# SparkFun_USDA_Watershed_Monitor.net
KiCad netlist of a schematic drawn in EAGLE
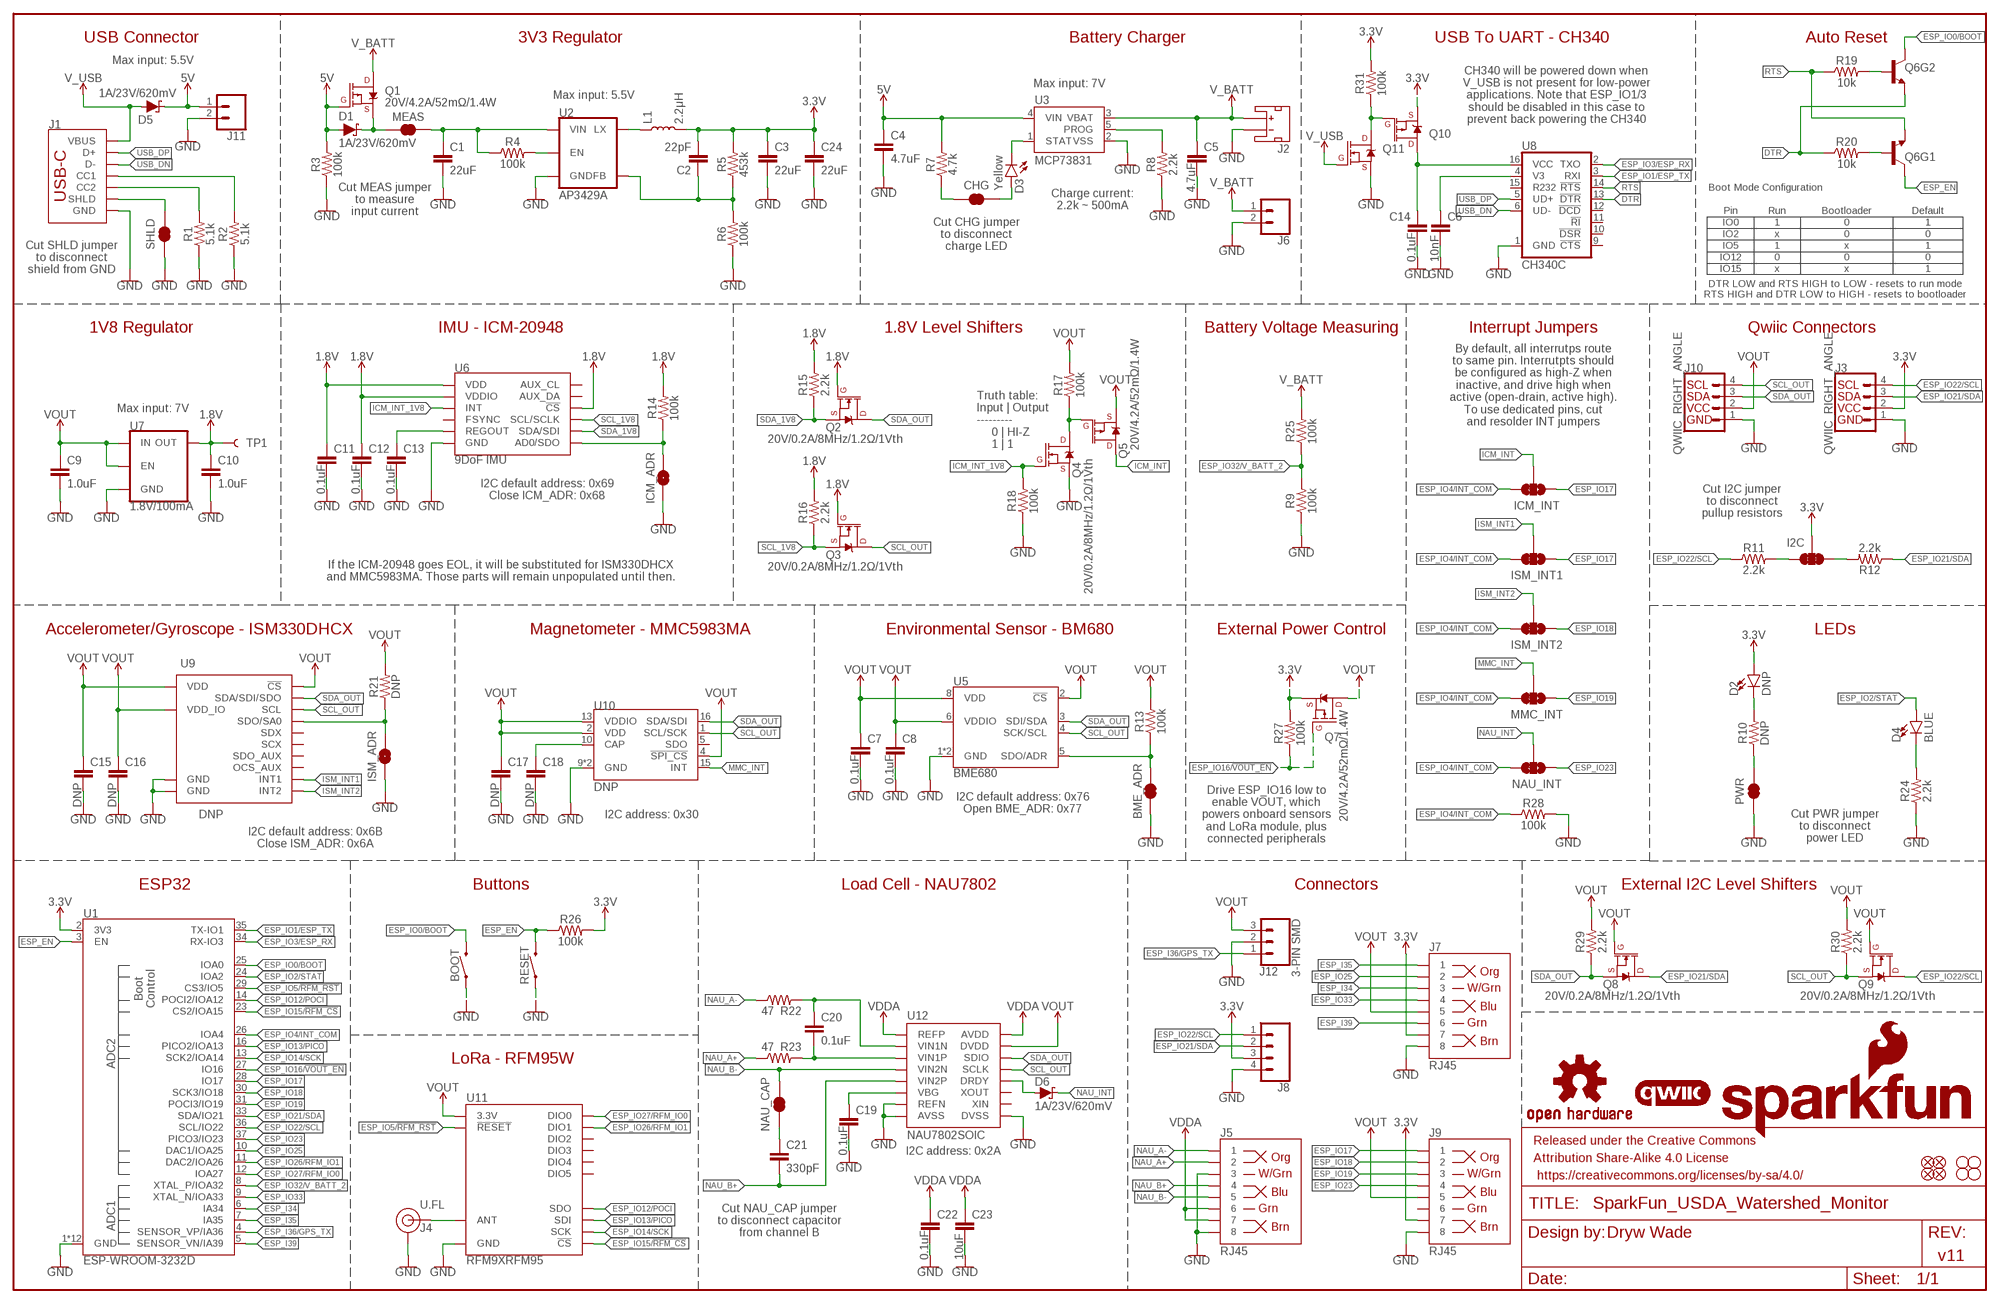
[diagram p0: schematic, sheet 1]

(export (version "E")
  (design (tool "Eeschema 10.0.6"))
  (components
    (comp (ref "BME_ADR")
      (value "JUMPER-SMT_2_NC_TRACE_SILK")
      (footprint "eagle-import:SMT-JUMPER_2_NC_TRACE_SILK")
      (libsource (lib "eagle-import") (part "JUMPER-SMT_2_NC_TRACE_SILK"))
    )
    (comp (ref "BOOT")
      (value "MOMENTARY-SWITCH-SPST-SMD-4.6X2.8MM")
      (footprint "eagle-import:TACTILE_SWITCH_SMD_4.6X2.8MM")
      (libsource (lib "eagle-import") (part "MOMENTARY-SWITCH-SPST-SMD-4.6X2.8MM"))
    )
    (comp (ref "C1")
      (value "22uF")
      (footprint "eagle-import:0805")
      (libsource (lib "eagle-import") (part "22UF-0805-16V-20%"))
    )
    (comp (ref "C2")
      (value "22pF")
      (footprint "eagle-import:0603")
      (libsource (lib "eagle-import") (part "22PF-0603-50V-5%"))
    )
    (comp (ref "C3")
      (value "22uF")
      (footprint "eagle-import:0805")
      (libsource (lib "eagle-import") (part "22UF-0805-16V-20%"))
    )
    (comp (ref "C4")
      (value "4.7uF")
      (footprint "eagle-import:0603")
      (libsource (lib "eagle-import") (part "4.7UF-0603-6.3V-(10%)"))
    )
    (comp (ref "C5")
      (value "4.7uF")
      (footprint "eagle-import:0603")
      (libsource (lib "eagle-import") (part "4.7UF-0603-6.3V-(10%)"))
    )
    (comp (ref "C6")
      (value "10nF")
      (footprint "eagle-import:0603")
      (libsource (lib "eagle-import") (part "10NF-0603-50V-10%"))
    )
    (comp (ref "C7")
      (value "0.1uF")
      (footprint "eagle-import:0603")
      (libsource (lib "eagle-import") (part "0.1UF-0603-25V-(+80/-20%)"))
    )
    (comp (ref "C8")
      (value "0.1uF")
      (footprint "eagle-import:0603")
      (libsource (lib "eagle-import") (part "0.1UF-0603-25V-(+80/-20%)"))
    )
    (comp (ref "C9")
      (value "1.0uF")
      (footprint "eagle-import:0603")
      (libsource (lib "eagle-import") (part "1.0UF-0603-16V-10%"))
    )
    (comp (ref "C10")
      (value "1.0uF")
      (footprint "eagle-import:0603")
      (libsource (lib "eagle-import") (part "1.0UF-0603-16V-10%"))
    )
    (comp (ref "C11")
      (value "0.1uF")
      (footprint "eagle-import:0603")
      (libsource (lib "eagle-import") (part "0.1UF-0603-25V-(+80/-20%)"))
    )
    (comp (ref "C12")
      (value "0.1uF")
      (footprint "eagle-import:0603")
      (libsource (lib "eagle-import") (part "0.1UF-0603-25V-(+80/-20%)"))
    )
    (comp (ref "C13")
      (value "0.1uF")
      (footprint "eagle-import:0603")
      (libsource (lib "eagle-import") (part "0.1UF-0603-25V-(+80/-20%)"))
    )
    (comp (ref "C14")
      (value "0.1uF")
      (footprint "eagle-import:0603")
      (libsource (lib "eagle-import") (part "0.1UF-0603-25V-(+80/-20%)"))
    )
    (comp (ref "C15")
      (value "DNP")
      (footprint "eagle-import:0603")
      (libsource (lib "eagle-import") (part "0.1UF-0603-25V-(+80/-20%)"))
    )
    (comp (ref "C16")
      (value "DNP")
      (footprint "eagle-import:0603")
      (libsource (lib "eagle-import") (part "0.1UF-0603-25V-(+80/-20%)"))
    )
    (comp (ref "C17")
      (value "DNP")
      (footprint "eagle-import:0603")
      (libsource (lib "eagle-import") (part "1.0UF-0603-16V-10%"))
    )
    (comp (ref "C18")
      (value "DNP")
      (footprint "eagle-import:0603")
      (libsource (lib "eagle-import") (part "10UF-0603-6.3V-20%"))
    )
    (comp (ref "C19")
      (value "0.1uF")
      (footprint "eagle-import:0603")
      (libsource (lib "eagle-import") (part "0.1UF-0603-25V-(+80/-20%)"))
    )
    (comp (ref "C20")
      (value "0.1uF")
      (footprint "eagle-import:0603")
      (libsource (lib "eagle-import") (part "0.1UF-0603-25V-(+80/-20%)"))
    )
    (comp (ref "C21")
      (value "330pF")
      (footprint "eagle-import:0603")
      (libsource (lib "eagle-import") (part "330PF-0603-50V-5%"))
    )
    (comp (ref "C22")
      (value "0.1uF")
      (footprint "eagle-import:0603")
      (libsource (lib "eagle-import") (part "0.1UF-0603-25V-(+80/-20%)"))
    )
    (comp (ref "C23")
      (value "10uF")
      (footprint "eagle-import:0603")
      (libsource (lib "eagle-import") (part "10UF-0603-6.3V-20%"))
    )
    (comp (ref "C24")
      (value "22uF")
      (footprint "eagle-import:0805")
      (libsource (lib "eagle-import") (part "22UF-0805-16V-20%"))
    )
    (comp (ref "CHG")
      (value "JUMPER-SMT_2_NC_TRACE_SILK")
      (footprint "eagle-import:SMT-JUMPER_2_NC_TRACE_SILK")
      (libsource (lib "eagle-import") (part "JUMPER-SMT_2_NC_TRACE_SILK"))
    )
    (comp (ref "D1")
      (value "1A/23V/620mV")
      (footprint "eagle-import:SOD-323")
      (libsource (lib "eagle-import") (part "DIODE-SCHOTTKY-BAT20J"))
    )
    (comp (ref "D2")
      (value "DNP")
      (footprint "eagle-import:LED-0603")
      (libsource (lib "eagle-import") (part "LED-RED_0603-KB"))
    )
    (comp (ref "D3")
      (value "Yellow")
      (footprint "eagle-import:LED-0603")
      (libsource (lib "eagle-import") (part "LED-YELLOW0603"))
    )
    (comp (ref "D4")
      (value "BLUE")
      (footprint "eagle-import:LED-0603")
      (libsource (lib "eagle-import") (part "LED-BLUE0603"))
    )
    (comp (ref "D5")
      (value "1A/23V/620mV")
      (footprint "eagle-import:SOD-323")
      (libsource (lib "eagle-import") (part "DIODE-SCHOTTKY-BAT20J"))
    )
    (comp (ref "D6")
      (value "1A/23V/620mV")
      (footprint "eagle-import:SOD-323")
      (libsource (lib "eagle-import") (part "DIODE-SCHOTTKY-BAT20J"))
    )
    (comp (ref "FD1")
      (value "FIDUCIAL1X2")
      (footprint "eagle-import:FIDUCIAL-1X2")
      (libsource (lib "eagle-import") (part "FIDUCIAL1X2"))
    )
    (comp (ref "FD2")
      (value "FIDUCIAL1X2")
      (footprint "eagle-import:FIDUCIAL-1X2")
      (libsource (lib "eagle-import") (part "FIDUCIAL1X2"))
    )
    (comp (ref "FD3")
      (value "FIDUCIAL1X2")
      (footprint "eagle-import:FIDUCIAL-1X2")
      (libsource (lib "eagle-import") (part "FIDUCIAL1X2"))
    )
    (comp (ref "FD4")
      (value "FIDUCIAL1X2")
      (footprint "eagle-import:FIDUCIAL-1X2")
      (libsource (lib "eagle-import") (part "FIDUCIAL1X2"))
    )
    (comp (ref "FRAME1")
      (value "FRAME-LEDGER")
      (footprint "eagle-import:CREATIVE_COMMONS")
      (libsource (lib "eagle-import") (part "FRAME-LEDGER"))
    )
    (comp (ref "H1")
      (value "STAND-OFF")
      (footprint "eagle-import:STAND-OFF")
      (libsource (lib "eagle-import") (part "STAND-OFF"))
    )
    (comp (ref "H2")
      (value "STAND-OFF")
      (footprint "eagle-import:STAND-OFF")
      (libsource (lib "eagle-import") (part "STAND-OFF"))
    )
    (comp (ref "H3")
      (value "STAND-OFF")
      (footprint "eagle-import:STAND-OFF")
      (libsource (lib "eagle-import") (part "STAND-OFF"))
    )
    (comp (ref "H4")
      (value "STAND-OFF")
      (footprint "eagle-import:STAND-OFF")
      (libsource (lib "eagle-import") (part "STAND-OFF"))
    )
    (comp (ref "I2C")
      (value "JUMPER-SMT_3_2-NC_TRACE_SILK")
      (footprint "eagle-import:SMT-JUMPER_3_2-NC_TRACE_SILK")
      (libsource (lib "eagle-import") (part "JUMPER-SMT_3_2-NC_TRACE_SILK"))
    )
    (comp (ref "ICM_ADR")
      (value "JUMPER-SMT_2_NO_SILK")
      (footprint "eagle-import:SMT-JUMPER_2_NO_SILK")
      (libsource (lib "eagle-import") (part "JUMPER-SMT_2_NO_SILK"))
    )
    (comp (ref "ICM_INT")
      (value "JUMPER-SMT_3_1-NC_TRACE_SILK")
      (footprint "eagle-import:SMT-JUMPER_3_1-NC_TRACE_SILK")
      (libsource (lib "eagle-import") (part "JUMPER-SMT_3_1-NC_TRACE_SILK"))
    )
    (comp (ref "ISM_ADR")
      (value "JUMPER-SMT_2_NO_SILK")
      (footprint "eagle-import:SMT-JUMPER_2_NO_SILK")
      (libsource (lib "eagle-import") (part "JUMPER-SMT_2_NO_SILK"))
    )
    (comp (ref "ISM_INT1")
      (value "JUMPER-SMT_3_1-NC_TRACE_SILK")
      (footprint "eagle-import:SMT-JUMPER_3_1-NC_TRACE_SILK")
      (libsource (lib "eagle-import") (part "JUMPER-SMT_3_1-NC_TRACE_SILK"))
    )
    (comp (ref "ISM_INT2")
      (value "JUMPER-SMT_3_1-NC_TRACE_SILK")
      (footprint "eagle-import:SMT-JUMPER_3_1-NC_TRACE_SILK")
      (libsource (lib "eagle-import") (part "JUMPER-SMT_3_1-NC_TRACE_SILK"))
    )
    (comp (ref "J1")
      (value "USB_C_2-LAYER_PADS")
      (footprint "eagle-import:USB-C-16P-2LAYER-PADS")
      (libsource (lib "eagle-import") (part "USB_C_2-LAYER_PADS"))
    )
    (comp (ref "J2")
      (value "JST_2MM_MALE")
      (footprint "eagle-import:JST-2-SMD")
      (libsource (lib "eagle-import") (part "JST_2MM_MALE"))
    )
    (comp (ref "J3")
      (value "QWIIC_RIGHT_ANGLE")
      (footprint "eagle-import:JST04_1MM_RA")
      (libsource (lib "eagle-import") (part "QWIIC_CONNECTORJS-1MM"))
    )
    (comp (ref "J4")
      (value "U.FL")
      (footprint "eagle-import:U.FL")
      (libsource (lib "eagle-import") (part "U.FL2PIN"))
    )
    (comp (ref "J5")
      (value "RJ45")
      (footprint "eagle-import:RJ45-8")
      (libsource (lib "eagle-import") (part "RJ45-8"))
    )
    (comp (ref "J6")
      (value "CONN_021X02_NO_SILK")
      (footprint "eagle-import:1X02_NO_SILK")
      (libsource (lib "eagle-import") (part "CONN_021X02_NO_SILK"))
    )
    (comp (ref "J7")
      (value "RJ45")
      (footprint "eagle-import:RJ45-8")
      (libsource (lib "eagle-import") (part "RJ45-8"))
    )
    (comp (ref "J8")
      (value "CONN_041X04_NO_SILK_NO_POP")
      (footprint "eagle-import:1X04_NO_SILK")
      (libsource (lib "eagle-import") (part "CONN_041X04_NO_SILK_NO_POP"))
    )
    (comp (ref "J9")
      (value "RJ45")
      (footprint "eagle-import:RJ45-8")
      (libsource (lib "eagle-import") (part "RJ45-8"))
    )
    (comp (ref "J10")
      (value "QWIIC_RIGHT_ANGLE")
      (footprint "eagle-import:JST04_1MM_RA")
      (libsource (lib "eagle-import") (part "QWIIC_CONNECTORJS-1MM"))
    )
    (comp (ref "J11")
      (value "CONN_021X02_NO_SILK")
      (footprint "eagle-import:1X02_NO_SILK")
      (libsource (lib "eagle-import") (part "CONN_021X02_NO_SILK"))
    )
    (comp (ref "J12")
      (value "3-PIN SMD")
      (footprint "eagle-import:JST-3-SMD")
      (libsource (lib "eagle-import") (part "CONN_03JST-SMD"))
    )
    (comp (ref "L1")
      (value "2.2μH")
      (footprint "eagle-import:INDUCTOR_4X4MM")
      (libsource (lib "eagle-import") (part "2.2μH-4X4-2.2μH-3A-45MOHM"))
    )
    (comp (ref "LOGO1")
      (value "SFE_LOGO_NAME_FLAME.1_INCH")
      (footprint "eagle-import:SFE_LOGO_NAME_FLAME_.1")
      (libsource (lib "eagle-import") (part "SFE_LOGO_NAME_FLAME.1_INCH"))
    )
    (comp (ref "LOGO2")
      (value "OSHW-LOGOS")
      (footprint "eagle-import:OSHW-LOGO-S")
      (libsource (lib "eagle-import") (part "OSHW-LOGOS"))
    )
    (comp (ref "LOGO3")
      (value "QWIIC_LOGO_4MM")
      (footprint "eagle-import:QWIIC_4MM")
      (libsource (lib "eagle-import") (part "QWIIC_LOGO_4MM"))
    )
    (comp (ref "MEAS")
      (value "JUMPER-COMBO_2_NC_TRACE")
      (footprint "eagle-import:COMBO-JUMPER_2_NC_TRACE")
      (libsource (lib "eagle-import") (part "JUMPER-COMBO_2_NC_TRACE"))
    )
    (comp (ref "MMC_INT")
      (value "JUMPER-SMT_3_1-NC_TRACE_SILK")
      (footprint "eagle-import:SMT-JUMPER_3_1-NC_TRACE_SILK")
      (libsource (lib "eagle-import") (part "JUMPER-SMT_3_1-NC_TRACE_SILK"))
    )
    (comp (ref "NAU_CAP")
      (value "JUMPER-SMT_2_NC_TRACE_SILK")
      (footprint "eagle-import:SMT-JUMPER_2_NC_TRACE_SILK")
      (libsource (lib "eagle-import") (part "JUMPER-SMT_2_NC_TRACE_SILK"))
    )
    (comp (ref "NAU_INT")
      (value "JUMPER-SMT_3_1-NC_TRACE_SILK")
      (footprint "eagle-import:SMT-JUMPER_3_1-NC_TRACE_SILK")
      (libsource (lib "eagle-import") (part "JUMPER-SMT_3_1-NC_TRACE_SILK"))
    )
    (comp (ref "PWR")
      (value "JUMPER-SMT_2_NC_TRACE_SILK")
      (footprint "eagle-import:SMT-JUMPER_2_NC_TRACE_SILK")
      (libsource (lib "eagle-import") (part "JUMPER-SMT_2_NC_TRACE_SILK"))
    )
    (comp (ref "Q1")
      (value "20V/4.2A/52mΩ/1.4W")
      (footprint "eagle-import:SOT23-3")
      (libsource (lib "eagle-import") (part "MOSFET_PCH-DMG2305UX-7"))
    )
    (comp (ref "Q2")
      (value "20V/0.2A/8MHz/1.2Ω/1Vth")
      (footprint "eagle-import:SOT-416FL")
      (libsource (lib "eagle-import") (part "MOSFET-NCH-RE1C002UNTCL"))
    )
    (comp (ref "Q3")
      (value "20V/0.2A/8MHz/1.2Ω/1Vth")
      (footprint "eagle-import:SOT-416FL")
      (libsource (lib "eagle-import") (part "MOSFET-NCH-RE1C002UNTCL"))
    )
    (comp (ref "Q4")
      (value "20V/0.2A/8MHz/1.2Ω/1Vth")
      (footprint "eagle-import:SOT-416FL")
      (libsource (lib "eagle-import") (part "MOSFET-NCH-RE1C002UNTCL"))
    )
    (comp (ref "Q5")
      (value "20V/4.2A/52mΩ/1.4W")
      (footprint "eagle-import:SOT23-3")
      (libsource (lib "eagle-import") (part "MOSFET_PCH-DMG2305UX-7"))
    )
    (comp (ref "Q6")
      (value "TRANS_NPN_DUAL-MBT3904DW1T1")
      (footprint "eagle-import:SC70-6")
      (libsource (lib "eagle-import") (part "TRANS_NPN_DUAL-MBT3904DW1T1"))
    )
    (comp (ref "Q7")
      (value "20V/4.2A/52mΩ/1.4W")
      (footprint "eagle-import:SOT23-3")
      (libsource (lib "eagle-import") (part "MOSFET_PCH-DMG2305UX-7"))
    )
    (comp (ref "Q8")
      (value "20V/0.2A/8MHz/1.2Ω/1Vth")
      (footprint "eagle-import:SOT-416FL")
      (libsource (lib "eagle-import") (part "MOSFET-NCH-RE1C002UNTCL"))
    )
    (comp (ref "Q9")
      (value "20V/0.2A/8MHz/1.2Ω/1Vth")
      (footprint "eagle-import:SOT-416FL")
      (libsource (lib "eagle-import") (part "MOSFET-NCH-RE1C002UNTCL"))
    )
    (comp (ref "Q10")
      (value "20V/4.2A/52mΩ/1.4W")
      (footprint "eagle-import:SOT23-3")
      (libsource (lib "eagle-import") (part "MOSFET_PCH-DMG2305UX-7"))
    )
    (comp (ref "Q11")
      (value "20V/0.2A/8MHz/1.2Ω/1Vth")
      (footprint "eagle-import:SOT-416FL")
      (libsource (lib "eagle-import") (part "MOSFET-NCH-RE1C002UNTCL"))
    )
    (comp (ref "R1")
      (value "5.1k")
      (footprint "eagle-import:0603")
      (libsource (lib "eagle-import") (part "5.1KOHM5.1KOHM-0603-1/10W-1%"))
    )
    (comp (ref "R2")
      (value "5.1k")
      (footprint "eagle-import:0603")
      (libsource (lib "eagle-import") (part "5.1KOHM5.1KOHM-0603-1/10W-1%"))
    )
    (comp (ref "R3")
      (value "100k")
      (footprint "eagle-import:0603")
      (libsource (lib "eagle-import") (part "100KOHM-0603-1/10W-1%"))
    )
    (comp (ref "R4")
      (value "100k")
      (footprint "eagle-import:0603")
      (libsource (lib "eagle-import") (part "100KOHM-0603-1/10W-1%"))
    )
    (comp (ref "R5")
      (value "453k")
      (footprint "eagle-import:0603")
      (libsource (lib "eagle-import") (part "453KOHM-0603-1/10W-1%"))
    )
    (comp (ref "R6")
      (value "100k")
      (footprint "eagle-import:0603")
      (libsource (lib "eagle-import") (part "100KOHM-0603-1/10W-1%"))
    )
    (comp (ref "R7")
      (value "4.7k")
      (footprint "eagle-import:0603")
      (libsource (lib "eagle-import") (part "4.7KOHM-0603-1/10W-1%"))
    )
    (comp (ref "R8")
      (value "2.2k")
      (footprint "eagle-import:0603")
      (libsource (lib "eagle-import") (part "2.2KOHM-0603-1/10W-1%"))
    )
    (comp (ref "R9")
      (value "100k")
      (footprint "eagle-import:0603")
      (libsource (lib "eagle-import") (part "100KOHM-0603-1/10W-1%"))
    )
    (comp (ref "R10")
      (value "DNP")
      (footprint "eagle-import:0603")
      (libsource (lib "eagle-import") (part "4.7KOHM-0603-1/10W-1%"))
    )
    (comp (ref "R11")
      (value "2.2k")
      (footprint "eagle-import:0603")
      (libsource (lib "eagle-import") (part "2.2KOHM-0603-1/10W-1%"))
    )
    (comp (ref "R12")
      (value "2.2k")
      (footprint "eagle-import:0603")
      (libsource (lib "eagle-import") (part "2.2KOHM-0603-1/10W-1%"))
    )
    (comp (ref "R13")
      (value "100k")
      (footprint "eagle-import:0603")
      (libsource (lib "eagle-import") (part "100KOHM-0603-1/10W-1%"))
    )
    (comp (ref "R14")
      (value "100k")
      (footprint "eagle-import:0603")
      (libsource (lib "eagle-import") (part "100KOHM-0603-1/10W-1%"))
    )
    (comp (ref "R15")
      (value "2.2k")
      (footprint "eagle-import:0603")
      (libsource (lib "eagle-import") (part "2.2KOHM-0603-1/10W-1%"))
    )
    (comp (ref "R16")
      (value "2.2k")
      (footprint "eagle-import:0603")
      (libsource (lib "eagle-import") (part "2.2KOHM-0603-1/10W-1%"))
    )
    (comp (ref "R17")
      (value "100k")
      (footprint "eagle-import:0603")
      (libsource (lib "eagle-import") (part "100KOHM-0603-1/10W-1%"))
    )
    (comp (ref "R18")
      (value "100k")
      (footprint "eagle-import:0603")
      (libsource (lib "eagle-import") (part "100KOHM-0603-1/10W-1%"))
    )
    (comp (ref "R19")
      (value "10k")
      (footprint "eagle-import:0603")
      (libsource (lib "eagle-import") (part "10KOHM-0603-1/10W-1%"))
    )
    (comp (ref "R20")
      (value "10k")
      (footprint "eagle-import:0603")
      (libsource (lib "eagle-import") (part "10KOHM-0603-1/10W-1%"))
    )
    (comp (ref "R21")
      (value "DNP")
      (footprint "eagle-import:0603")
      (libsource (lib "eagle-import") (part "100KOHM-0603-1/10W-1%"))
    )
    (comp (ref "R22")
      (value "47")
      (footprint "eagle-import:0603")
      (libsource (lib "eagle-import") (part "47OHM-0603-1/10W-1%"))
    )
    (comp (ref "R23")
      (value "47")
      (footprint "eagle-import:0603")
      (libsource (lib "eagle-import") (part "47OHM-0603-1/10W-1%"))
    )
    (comp (ref "R24")
      (value "2.2k")
      (footprint "eagle-import:0603")
      (libsource (lib "eagle-import") (part "2.2KOHM-0603-1/10W-1%"))
    )
    (comp (ref "R25")
      (value "100k")
      (footprint "eagle-import:0603")
      (libsource (lib "eagle-import") (part "100KOHM-0603-1/10W-1%"))
    )
    (comp (ref "R26")
      (value "100k")
      (footprint "eagle-import:0603")
      (libsource (lib "eagle-import") (part "100KOHM-0603-1/10W-1%"))
    )
    (comp (ref "R27")
      (value "100k")
      (footprint "eagle-import:0603")
      (libsource (lib "eagle-import") (part "100KOHM-0603-1/10W-1%"))
    )
    (comp (ref "R28")
      (value "100k")
      (footprint "eagle-import:0603")
      (libsource (lib "eagle-import") (part "100KOHM-0603-1/10W-1%"))
    )
    (comp (ref "R29")
      (value "2.2k")
      (footprint "eagle-import:0603")
      (libsource (lib "eagle-import") (part "2.2KOHM-0603-1/10W-1%"))
    )
    (comp (ref "R30")
      (value "2.2k")
      (footprint "eagle-import:0603")
      (libsource (lib "eagle-import") (part "2.2KOHM-0603-1/10W-1%"))
    )
    (comp (ref "R31")
      (value "100k")
      (footprint "eagle-import:0603")
      (libsource (lib "eagle-import") (part "100KOHM-0603-1/10W-1%"))
    )
    (comp (ref "RESET")
      (value "MOMENTARY-SWITCH-SPST-SMD-4.6X2.8MM")
      (footprint "eagle-import:TACTILE_SWITCH_SMD_4.6X2.8MM")
      (libsource (lib "eagle-import") (part "MOMENTARY-SWITCH-SPST-SMD-4.6X2.8MM"))
    )
    (comp (ref "SHLD")
      (value "JUMPER-SMT_2_NC_TRACE_SILK")
      (footprint "eagle-import:SMT-JUMPER_2_NC_TRACE_SILK")
      (libsource (lib "eagle-import") (part "JUMPER-SMT_2_NC_TRACE_SILK"))
    )
    (comp (ref "TP1")
      (value "TEST-POINT3X4")
      (footprint "eagle-import:PAD.03X.04")
      (libsource (lib "eagle-import") (part "TEST-POINT3X4"))
    )
    (comp (ref "U1")
      (value "ESP-WROOM-3232D")
      (footprint "eagle-import:ESP-WROOM-32D")
      (libsource (lib "eagle-import") (part "ESP-WROOM-3232D"))
    )
    (comp (ref "U2")
      (value "AP3429A")
      (footprint "eagle-import:SOT23-5")
      (libsource (lib "eagle-import") (part "AP3429/A"))
    )
    (comp (ref "U3")
      (value "MCP73831")
      (footprint "eagle-import:SOT23-5")
      (libsource (lib "eagle-import") (part "MCP73831"))
    )
    (comp (ref "U5")
      (value "BME680")
      (footprint "eagle-import:LGA3.0X3.0")
      (libsource (lib "eagle-import") (part "BME680-LGA"))
    )
    (comp (ref "U6")
      (value "9DoF IMU")
      (footprint "eagle-import:QFN24-3X3-ICM-20948")
      (libsource (lib "eagle-import") (part "ICM-20948"))
    )
    (comp (ref "U7")
      (value "1.8V/100mA")
      (footprint "eagle-import:SC70")
      (libsource (lib "eagle-import") (part "V_REG_SP6214-1.8V"))
    )
    (comp (ref "U8")
      (value "CH340C")
      (footprint "eagle-import:SO016")
      (libsource (lib "eagle-import") (part "CH340C"))
    )
    (comp (ref "U9")
      (value "DNP")
      (footprint "eagle-import:LGA-14L")
      (libsource (lib "eagle-import") (part "ISM330DHCX"))
    )
    (comp (ref "U10")
      (value "DNP")
      (footprint "eagle-import:LGA-16-3X3MM-4X4PINS")
      (libsource (lib "eagle-import") (part "MMC5983MA_QFN16"))
    )
    (comp (ref "U11")
      (value "RFM9XRFM95")
      (footprint "eagle-import:RFM95")
      (libsource (lib "eagle-import") (part "RFM9XRFM95"))
    )
    (comp (ref "U12")
      (value "NAU7802SOIC")
      (footprint "eagle-import:SO16")
      (libsource (lib "eagle-import") (part "NAU7802SOIC"))
    )
  )
  (nets
    (net (code "1") (name "/ESP_IO5{slash}~{RFM_RST}") (class "Default")
      (node (ref "U1") (pin "29") (pinfunction "CS3/IO5_29") (pintype "bidirectional"))
      (node (ref "U11") (pin "!RESET") (pinfunction "~{RESET}_!RESET") (pintype "bidirectional"))
    )
    (net (code "2") (name "/ESP_IO15{slash}~{RFM_CS}") (class "Default")
      (node (ref "U1") (pin "23") (pinfunction "CS2/IOA15_23") (pintype "bidirectional"))
      (node (ref "U11") (pin "NSS") (pinfunction "~{CS}_NSS") (pintype "bidirectional"))
    )
    (net (code "3") (name "/ESP_IO16{slash}~{VOUT_EN}") (class "Default")
      (node (ref "Q7") (pin "1") (pinfunction "G_1") (pintype "bidirectional"))
      (node (ref "R27") (pin "1") (pinfunction "1_1") (pintype "passive"))
      (node (ref "U1") (pin "27") (pinfunction "IO16_27") (pintype "bidirectional"))
    )
    (net (code "4") (name "1.8V") (class "Default")
      (node (ref "C10") (pin "1") (pinfunction "1_1") (pintype "passive"))
      (node (ref "C11") (pin "1") (pinfunction "1_1") (pintype "passive"))
      (node (ref "C12") (pin "1") (pinfunction "1_1") (pintype "passive"))
      (node (ref "Q2") (pin "1") (pinfunction "G_1") (pintype "bidirectional"))
      (node (ref "Q3") (pin "1") (pinfunction "G_1") (pintype "bidirectional"))
      (node (ref "R14") (pin "2") (pinfunction "2_2") (pintype "passive"))
      (node (ref "R15") (pin "2") (pinfunction "2_2") (pintype "passive"))
      (node (ref "R16") (pin "2") (pinfunction "2_2") (pintype "passive"))
      (node (ref "TP1") (pin "1") (pinfunction "1_1") (pintype "bidirectional"))
      (node (ref "U6") (pin "13") (pinfunction "VDD_13") (pintype "bidirectional"))
      (node (ref "U6") (pin "22") (pinfunction "~{CS}_22") (pintype "bidirectional"))
      (node (ref "U6") (pin "8") (pinfunction "VDDIO_8") (pintype "bidirectional"))
      (node (ref "U7") (pin "5") (pinfunction "OUT_5") (pintype "passive"))
    )
    (net (code "5") (name "3.3V") (class "Default")
      (node (ref "C2") (pin "2") (pinfunction "2_2") (pintype "passive"))
      (node (ref "C24") (pin "1") (pinfunction "1_1") (pintype "passive"))
      (node (ref "C3") (pin "1") (pinfunction "1_1") (pintype "passive"))
      (node (ref "D2") (pin "A") (pinfunction "A_A") (pintype "passive"))
      (node (ref "I2C") (pin "2") (pinfunction "2_2") (pintype "passive"))
      (node (ref "J3") (pin "2") (pinfunction "2_2") (pintype "power_in"))
      (node (ref "J7") (pin "7") (pinfunction "7_7") (pintype "bidirectional"))
      (node (ref "J8") (pin "3") (pinfunction "3_3") (pintype "passive"))
      (node (ref "J9") (pin "7") (pinfunction "7_7") (pintype "bidirectional"))
      (node (ref "L1") (pin "P$2") (pinfunction "2_P$2") (pintype "passive"))
      (node (ref "Q10") (pin "2") (pinfunction "S_2") (pintype "bidirectional"))
      (node (ref "Q7") (pin "2") (pinfunction "S_2") (pintype "bidirectional"))
      (node (ref "R26") (pin "2") (pinfunction "2_2") (pintype "passive"))
      (node (ref "R27") (pin "2") (pinfunction "2_2") (pintype "passive"))
      (node (ref "R31") (pin "2") (pinfunction "2_2") (pintype "passive"))
      (node (ref "R5") (pin "2") (pinfunction "2_2") (pintype "passive"))
      (node (ref "U1") (pin "2") (pinfunction "3V3_2") (pintype "bidirectional"))
    )
    (net (code "6") (name "5V") (class "Default")
      (node (ref "C4") (pin "1") (pinfunction "1_1") (pintype "passive"))
      (node (ref "D1") (pin "A") (pinfunction "A_A") (pintype "passive"))
      (node (ref "D5") (pin "C") (pinfunction "C_C") (pintype "passive"))
      (node (ref "J11") (pin "1") (pinfunction "1_1") (pintype "passive"))
      (node (ref "Q1") (pin "1") (pinfunction "G_1") (pintype "bidirectional"))
      (node (ref "R3") (pin "2") (pinfunction "2_2") (pintype "passive"))
      (node (ref "R7") (pin "2") (pinfunction "2_2") (pintype "passive"))
      (node (ref "U3") (pin "4") (pinfunction "VIN_4") (pintype "power_in"))
    )
    (net (code "7") (name "DTR") (class "Default")
      (node (ref "Q6") (pin "1") (pinfunction "E_1") (pintype "passive"))
      (node (ref "R20") (pin "1") (pinfunction "1_1") (pintype "passive"))
      (node (ref "U8") (pin "13") (pinfunction "~{DTR}_13") (pintype "bidirectional"))
    )
    (net (code "8") (name "ESP_EN") (class "Default")
      (node (ref "Q6") (pin "3") (pinfunction "C_3") (pintype "passive"))
      (node (ref "R26") (pin "1") (pinfunction "1_1") (pintype "passive"))
      (node (ref "RESET") (pin "3") (pinfunction "2_3") (pintype "passive"))
      (node (ref "RESET") (pin "4") (pinfunction "2_4") (pintype "passive"))
      (node (ref "U1") (pin "3") (pinfunction "EN_3") (pintype "bidirectional"))
    )
    (net (code "9") (name "ESP_I34") (class "Default")
      (node (ref "J7") (pin "3") (pinfunction "3_3") (pintype "bidirectional"))
      (node (ref "U1") (pin "6") (pinfunction "IA34_6") (pintype "bidirectional"))
    )
    (net (code "10") (name "ESP_I35") (class "Default")
      (node (ref "J7") (pin "1") (pinfunction "1_1") (pintype "bidirectional"))
      (node (ref "U1") (pin "7") (pinfunction "IA35_7") (pintype "bidirectional"))
    )
    (net (code "11") (name "ESP_I36{slash}GPS_TX") (class "Default")
      (node (ref "J12") (pin "1") (pinfunction "3_1") (pintype "passive"))
      (node (ref "U1") (pin "4") (pinfunction "SENSOR_VP/IA36_4") (pintype "bidirectional"))
    )
    (net (code "12") (name "ESP_I39") (class "Default")
      (node (ref "J7") (pin "6") (pinfunction "6_6") (pintype "bidirectional"))
      (node (ref "U1") (pin "5") (pinfunction "SENSOR_VN/IA39_5") (pintype "bidirectional"))
    )
    (net (code "13") (name "ESP_IO0{slash}BOOT") (class "Default")
      (node (ref "BOOT") (pin "3") (pinfunction "2_3") (pintype "passive"))
      (node (ref "BOOT") (pin "4") (pinfunction "2_4") (pintype "passive"))
      (node (ref "Q6") (pin "6") (pinfunction "C_6") (pintype "passive"))
      (node (ref "U1") (pin "25") (pinfunction "IOA0_25") (pintype "bidirectional"))
    )
    (net (code "14") (name "ESP_IO1{slash}ESP_TX") (class "Default")
      (node (ref "U1") (pin "35") (pinfunction "TX-IO1_35") (pintype "bidirectional"))
      (node (ref "U8") (pin "3") (pinfunction "RXI_3") (pintype "bidirectional"))
    )
    (net (code "15") (name "ESP_IO2{slash}STAT") (class "Default")
      (node (ref "D4") (pin "A") (pinfunction "A_A") (pintype "passive"))
      (node (ref "U1") (pin "24") (pinfunction "IOA2_24") (pintype "bidirectional"))
    )
    (net (code "16") (name "ESP_IO3{slash}ESP_RX") (class "Default")
      (node (ref "U1") (pin "34") (pinfunction "RX-IO3_34") (pintype "bidirectional"))
      (node (ref "U8") (pin "2") (pinfunction "TXO_2") (pintype "bidirectional"))
    )
    (net (code "17") (name "ESP_IO4{slash}INT_COM") (class "Default")
      (node (ref "ICM_INT") (pin "3") (pinfunction "3_3") (pintype "passive"))
      (node (ref "ISM_INT1") (pin "3") (pinfunction "3_3") (pintype "passive"))
      (node (ref "ISM_INT2") (pin "3") (pinfunction "3_3") (pintype "passive"))
      (node (ref "MMC_INT") (pin "3") (pinfunction "3_3") (pintype "passive"))
      (node (ref "NAU_INT") (pin "3") (pinfunction "3_3") (pintype "passive"))
      (node (ref "R28") (pin "1") (pinfunction "1_1") (pintype "passive"))
      (node (ref "U1") (pin "26") (pinfunction "IOA4_26") (pintype "bidirectional"))
    )
    (net (code "18") (name "ESP_IO12{slash}POCI") (class "Default")
      (node (ref "U1") (pin "14") (pinfunction "POCI2/IOA12_14") (pintype "bidirectional"))
      (node (ref "U11") (pin "SDO") (pinfunction "SDO_SDO") (pintype "bidirectional"))
    )
    (net (code "19") (name "ESP_IO13{slash}PICO") (class "Default")
      (node (ref "U1") (pin "16") (pinfunction "PICO2/IOA13_16") (pintype "bidirectional"))
      (node (ref "U11") (pin "SDI") (pinfunction "SDI_SDI") (pintype "bidirectional"))
    )
    (net (code "20") (name "ESP_IO14{slash}SCK") (class "Default")
      (node (ref "U1") (pin "13") (pinfunction "SCK2/IOA14_13") (pintype "bidirectional"))
      (node (ref "U11") (pin "SCK") (pinfunction "SCK_SCK") (pintype "bidirectional"))
    )
    (net (code "21") (name "ESP_IO17") (class "Default")
      (node (ref "ICM_INT") (pin "1") (pinfunction "1_1") (pintype "passive"))
      (node (ref "ISM_INT1") (pin "1") (pinfunction "1_1") (pintype "passive"))
      (node (ref "J9") (pin "1") (pinfunction "1_1") (pintype "bidirectional"))
      (node (ref "U1") (pin "28") (pinfunction "IO17_28") (pintype "bidirectional"))
    )
    (net (code "22") (name "ESP_IO18") (class "Default")
      (node (ref "ISM_INT2") (pin "1") (pinfunction "1_1") (pintype "passive"))
      (node (ref "J9") (pin "2") (pinfunction "2_2") (pintype "bidirectional"))
      (node (ref "U1") (pin "30") (pinfunction "SCK3/IO18_30") (pintype "bidirectional"))
    )
    (net (code "23") (name "ESP_IO19") (class "Default")
      (node (ref "J9") (pin "3") (pinfunction "3_3") (pintype "bidirectional"))
      (node (ref "MMC_INT") (pin "1") (pinfunction "1_1") (pintype "passive"))
      (node (ref "U1") (pin "31") (pinfunction "POCI3/IO19_31") (pintype "bidirectional"))
    )
    (net (code "24") (name "ESP_IO21{slash}SDA") (class "Default")
      (node (ref "J3") (pin "3") (pinfunction "3_3") (pintype "passive"))
      (node (ref "J8") (pin "2") (pinfunction "2_2") (pintype "passive"))
      (node (ref "Q8") (pin "3") (pinfunction "D_3") (pintype "bidirectional"))
      (node (ref "R12") (pin "1") (pinfunction "1_1") (pintype "passive"))
      (node (ref "U1") (pin "33") (pinfunction "SDA/IO21_33") (pintype "bidirectional"))
    )
    (net (code "25") (name "ESP_IO22{slash}SCL") (class "Default")
      (node (ref "J3") (pin "4") (pinfunction "4_4") (pintype "passive"))
      (node (ref "J8") (pin "1") (pinfunction "1_1") (pintype "passive"))
      (node (ref "Q9") (pin "3") (pinfunction "D_3") (pintype "bidirectional"))
      (node (ref "R11") (pin "1") (pinfunction "1_1") (pintype "passive"))
      (node (ref "U1") (pin "36") (pinfunction "SCL/IO22_36") (pintype "bidirectional"))
    )
    (net (code "26") (name "ESP_IO23") (class "Default")
      (node (ref "J9") (pin "4") (pinfunction "4_4") (pintype "bidirectional"))
      (node (ref "NAU_INT") (pin "1") (pinfunction "1_1") (pintype "passive"))
      (node (ref "U1") (pin "37") (pinfunction "PICO3/IO23_37") (pintype "bidirectional"))
    )
    (net (code "27") (name "ESP_IO25") (class "Default")
      (node (ref "J7") (pin "2") (pinfunction "2_2") (pintype "bidirectional"))
      (node (ref "U1") (pin "10") (pinfunction "DAC1/IOA25_10") (pintype "bidirectional"))
    )
    (net (code "28") (name "ESP_IO26{slash}RFM_IO1") (class "Default")
      (node (ref "U1") (pin "11") (pinfunction "DAC2/IOA26_11") (pintype "bidirectional"))
      (node (ref "U11") (pin "DIO1") (pinfunction "DIO1_DIO1") (pintype "bidirectional"))
    )
    (net (code "29") (name "ESP_IO27{slash}RFM_IO0") (class "Default")
      (node (ref "U1") (pin "12") (pinfunction "IOA27_12") (pintype "bidirectional"))
      (node (ref "U11") (pin "DIO0") (pinfunction "DIO0_DIO0") (pintype "bidirectional"))
    )
    (net (code "30") (name "ESP_IO32{slash}V_BATT_2") (class "Default")
      (node (ref "R25") (pin "1") (pinfunction "1_1") (pintype "passive"))
      (node (ref "R9") (pin "2") (pinfunction "2_2") (pintype "passive"))
      (node (ref "U1") (pin "8") (pinfunction "XTAL_P/IOA32_8") (pintype "bidirectional"))
    )
    (net (code "31") (name "ESP_IO33") (class "Default")
      (node (ref "J7") (pin "4") (pinfunction "4_4") (pintype "bidirectional"))
      (node (ref "U1") (pin "9") (pinfunction "XTAL_N/IOA33_9") (pintype "bidirectional"))
    )
    (net (code "32") (name "GND") (class "Default")
      (node (ref "BME_ADR") (pin "1") (pinfunction "1_1") (pintype "passive"))
      (node (ref "BOOT") (pin "1") (pinfunction "1_1") (pintype "passive"))
      (node (ref "BOOT") (pin "2") (pinfunction "1_2") (pintype "passive"))
      (node (ref "C1") (pin "2") (pinfunction "2_2") (pintype "passive"))
      (node (ref "C10") (pin "2") (pinfunction "2_2") (pintype "passive"))
      (node (ref "C11") (pin "2") (pinfunction "2_2") (pintype "passive"))
      (node (ref "C12") (pin "2") (pinfunction "2_2") (pintype "passive"))
      (node (ref "C13") (pin "2") (pinfunction "2_2") (pintype "passive"))
      (node (ref "C14") (pin "2") (pinfunction "2_2") (pintype "passive"))
      (node (ref "C15") (pin "2") (pinfunction "2_2") (pintype "passive"))
      (node (ref "C16") (pin "2") (pinfunction "2_2") (pintype "passive"))
      (node (ref "C17") (pin "2") (pinfunction "2_2") (pintype "passive"))
      (node (ref "C18") (pin "2") (pinfunction "2_2") (pintype "passive"))
      (node (ref "C19") (pin "2") (pinfunction "2_2") (pintype "passive"))
      (node (ref "C22") (pin "2") (pinfunction "2_2") (pintype "passive"))
      (node (ref "C23") (pin "2") (pinfunction "2_2") (pintype "passive"))
      (node (ref "C24") (pin "2") (pinfunction "2_2") (pintype "passive"))
      (node (ref "C3") (pin "2") (pinfunction "2_2") (pintype "passive"))
      (node (ref "C4") (pin "2") (pinfunction "2_2") (pintype "passive"))
      (node (ref "C5") (pin "2") (pinfunction "2_2") (pintype "passive"))
      (node (ref "C6") (pin "2") (pinfunction "2_2") (pintype "passive"))
      (node (ref "C7") (pin "2") (pinfunction "2_2") (pintype "passive"))
      (node (ref "C8") (pin "2") (pinfunction "2_2") (pintype "passive"))
      (node (ref "C9") (pin "2") (pinfunction "2_2") (pintype "passive"))
      (node (ref "ICM_ADR") (pin "1") (pinfunction "1_1") (pintype "passive"))
      (node (ref "ISM_ADR") (pin "1") (pinfunction "1_1") (pintype "passive"))
      (node (ref "J1") (pin "GND") (pinfunction "GND_GND") (pintype "bidirectional"))
      (node (ref "J1") (pin "GND2") (pinfunction "GND_GND2") (pintype "bidirectional"))
      (node (ref "J10") (pin "1") (pinfunction "1_1") (pintype "power_in"))
      (node (ref "J11") (pin "2") (pinfunction "2_2") (pintype "passive"))
      (node (ref "J12") (pin "2") (pinfunction "2_2") (pintype "passive"))
      (node (ref "J2") (pin "1") (pinfunction "-_1") (pintype "bidirectional"))
      (node (ref "J3") (pin "1") (pinfunction "1_1") (pintype "power_in"))
      (node (ref "J4") (pin "1") (pinfunction "GND_1") (pintype "bidirectional"))
      (node (ref "J4") (pin "2") (pinfunction "GND_2") (pintype "bidirectional"))
      (node (ref "J5") (pin "3") (pinfunction "3_3") (pintype "bidirectional"))
      (node (ref "J5") (pin "8") (pinfunction "8_8") (pintype "bidirectional"))
      (node (ref "J6") (pin "2") (pinfunction "2_2") (pintype "passive"))
      (node (ref "J7") (pin "8") (pinfunction "8_8") (pintype "bidirectional"))
      (node (ref "J8") (pin "4") (pinfunction "4_4") (pintype "passive"))
      (node (ref "J9") (pin "8") (pinfunction "8_8") (pintype "bidirectional"))
      (node (ref "PWR") (pin "1") (pinfunction "1_1") (pintype "passive"))
      (node (ref "Q11") (pin "2") (pinfunction "S_2") (pintype "bidirectional"))
      (node (ref "Q4") (pin "2") (pinfunction "S_2") (pintype "bidirectional"))
      (node (ref "R1") (pin "1") (pinfunction "1_1") (pintype "passive"))
      (node (ref "R18") (pin "1") (pinfunction "1_1") (pintype "passive"))
      (node (ref "R2") (pin "1") (pinfunction "1_1") (pintype "passive"))
      (node (ref "R24") (pin "1") (pinfunction "1_1") (pintype "passive"))
      (node (ref "R28") (pin "2") (pinfunction "2_2") (pintype "passive"))
      (node (ref "R3") (pin "1") (pinfunction "1_1") (pintype "passive"))
      (node (ref "R6") (pin "1") (pinfunction "1_1") (pintype "passive"))
      (node (ref "R8") (pin "1") (pinfunction "1_1") (pintype "passive"))
      (node (ref "R9") (pin "1") (pinfunction "1_1") (pintype "passive"))
      (node (ref "RESET") (pin "1") (pinfunction "1_1") (pintype "passive"))
      (node (ref "RESET") (pin "2") (pinfunction "1_2") (pintype "passive"))
      (node (ref "SHLD") (pin "1") (pinfunction "1_1") (pintype "passive"))
      (node (ref "U1") (pin "1") (pinfunction "GND_1") (pintype "bidirectional"))
      (node (ref "U1") (pin "15") (pinfunction "GND_15") (pintype "bidirectional"))
      (node (ref "U1") (pin "38") (pinfunction "GND_38") (pintype "bidirectional"))
      (node (ref "U1") (pin "GND") (pinfunction "GND_GND") (pintype "bidirectional"))
      (node (ref "U1") (pin "GNDT1") (pinfunction "GND_GNDT1") (pintype "bidirectional"))
      (node (ref "U1") (pin "GNDT2") (pinfunction "GND_GNDT2") (pintype "bidirectional"))
      (node (ref "U1") (pin "GNDT3") (pinfunction "GND_GNDT3") (pintype "bidirectional"))
      (node (ref "U1") (pin "GNDT4") (pinfunction "GND_GNDT4") (pintype "bidirectional"))
      (node (ref "U1") (pin "GNDT5") (pinfunction "GND_GNDT5") (pintype "bidirectional"))
      (node (ref "U1") (pin "GNDT6") (pinfunction "GND_GNDT6") (pintype "bidirectional"))
      (node (ref "U1") (pin "GNDT7") (pinfunction "GND_GNDT7") (pintype "bidirectional"))
      (node (ref "U1") (pin "GNDT8") (pinfunction "GND_GNDT8") (pintype "bidirectional"))
      (node (ref "U10") (pin "11") (pinfunction "GND_11") (pintype "power_in"))
      (node (ref "U10") (pin "9") (pinfunction "GND_9") (pintype "power_in"))
      (node (ref "U11") (pin "GND@1") (pinfunction "GND_GND@1") (pintype "bidirectional"))
      (node (ref "U11") (pin "GND@2") (pinfunction "GND_GND@2") (pintype "bidirectional"))
      (node (ref "U11") (pin "GND@3") (pinfunction "GND_GND@3") (pintype "bidirectional"))
      (node (ref "U12") (pin "7") (pinfunction "REFN_7") (pintype "bidirectional"))
      (node (ref "U12") (pin "8") (pinfunction "AVSS_8") (pintype "bidirectional"))
      (node (ref "U12") (pin "9") (pinfunction "DVSS_9") (pintype "bidirectional"))
      (node (ref "U2") (pin "2") (pinfunction "GND_2") (pintype "input"))
      (node (ref "U3") (pin "2") (pinfunction "VSS_2") (pintype "power_in"))
      (node (ref "U5") (pin "1") (pinfunction "GND_1") (pintype "bidirectional"))
      (node (ref "U5") (pin "7") (pinfunction "GND_7") (pintype "bidirectional"))
      (node (ref "U6") (pin "18") (pinfunction "GND_18") (pintype "bidirectional"))
      (node (ref "U6") (pin "20") (pinfunction "GND_20") (pintype "bidirectional"))
      (node (ref "U7") (pin "2") (pinfunction "GND_2") (pintype "input"))
      (node (ref "U8") (pin "1") (pinfunction "GND_1") (pintype "bidirectional"))
      (node (ref "U9") (pin "P6") (pinfunction "GND_P6") (pintype "power_in"))
      (node (ref "U9") (pin "P7") (pinfunction "GND_P7") (pintype "power_in"))
    )
    (net (code "33") (name "ICM_INT") (class "Default")
      (node (ref "ICM_INT") (pin "2") (pinfunction "2_2") (pintype "passive"))
      (node (ref "Q5") (pin "3") (pinfunction "D_3") (pintype "bidirectional"))
    )
    (net (code "34") (name "ICM_INT_1V8") (class "Default")
      (node (ref "Q4") (pin "1") (pinfunction "G_1") (pintype "bidirectional"))
      (node (ref "R18") (pin "2") (pinfunction "2_2") (pintype "passive"))
      (node (ref "U6") (pin "12") (pinfunction "INT_12") (pintype "bidirectional"))
    )
    (net (code "35") (name "ISM_INT1") (class "Default")
      (node (ref "ISM_INT1") (pin "2") (pinfunction "2_2") (pintype "passive"))
      (node (ref "U9") (pin "P4") (pinfunction "INT1_P4") (pintype "bidirectional"))
    )
    (net (code "36") (name "ISM_INT2") (class "Default")
      (node (ref "ISM_INT2") (pin "2") (pinfunction "2_2") (pintype "passive"))
      (node (ref "U9") (pin "P9") (pinfunction "INT2_P9") (pintype "bidirectional"))
    )
    (net (code "37") (name "MMC_INT") (class "Default")
      (node (ref "MMC_INT") (pin "2") (pinfunction "2_2") (pintype "passive"))
      (node (ref "U10") (pin "15") (pinfunction "INT_15") (pintype "output"))
    )
    (net (code "38") (name "NAU_A+") (class "Default")
      (node (ref "J5") (pin "2") (pinfunction "2_2") (pintype "bidirectional"))
      (node (ref "R23") (pin "1") (pinfunction "1_1") (pintype "passive"))
    )
    (net (code "39") (name "NAU_A-") (class "Default")
      (node (ref "J5") (pin "1") (pinfunction "1_1") (pintype "bidirectional"))
      (node (ref "R22") (pin "1") (pinfunction "1_1") (pintype "passive"))
    )
    (net (code "40") (name "NAU_B+") (class "Default")
      (node (ref "C21") (pin "2") (pinfunction "2_2") (pintype "passive"))
      (node (ref "J5") (pin "4") (pinfunction "4_4") (pintype "bidirectional"))
      (node (ref "U12") (pin "5") (pinfunction "VIN2P_5") (pintype "bidirectional"))
    )
    (net (code "41") (name "NAU_B-") (class "Default")
      (node (ref "J5") (pin "5") (pinfunction "5_5") (pintype "bidirectional"))
      (node (ref "NAU_CAP") (pin "2") (pinfunction "2_2") (pintype "passive"))
      (node (ref "U12") (pin "4") (pinfunction "VIN2N_4") (pintype "bidirectional"))
    )
    (net (code "42") (name "NAU_INT") (class "Default")
      (node (ref "D6") (pin "C") (pinfunction "C_C") (pintype "passive"))
      (node (ref "NAU_INT") (pin "2") (pinfunction "2_2") (pintype "passive"))
    )
    (net (code "43") (name "Net-(C21-Pad1)") (class "Default")
      (node (ref "C21") (pin "1") (pinfunction "1_1") (pintype "passive"))
      (node (ref "NAU_CAP") (pin "1") (pinfunction "1_1") (pintype "passive"))
    )
    (net (code "44") (name "Net-(CHG-Pad1)") (class "Default")
      (node (ref "CHG") (pin "1") (pinfunction "1_1") (pintype "passive"))
      (node (ref "R7") (pin "1") (pinfunction "1_1") (pintype "passive"))
    )
    (net (code "45") (name "Net-(CHG-Pad2)") (class "Default")
      (node (ref "CHG") (pin "2") (pinfunction "2_2") (pintype "passive"))
      (node (ref "D3") (pin "A") (pinfunction "A_A") (pintype "passive"))
    )
    (net (code "46") (name "Net-(D2-PadC)") (class "Default")
      (node (ref "D2") (pin "C") (pinfunction "C_C") (pintype "passive"))
      (node (ref "R10") (pin "2") (pinfunction "2_2") (pintype "passive"))
    )
    (net (code "47") (name "Net-(D4-PadC)") (class "Default")
      (node (ref "D4") (pin "C") (pinfunction "C_C") (pintype "passive"))
      (node (ref "R24") (pin "2") (pinfunction "2_2") (pintype "passive"))
    )
    (net (code "48") (name "Net-(I2C-Pad1)") (class "Default")
      (node (ref "I2C") (pin "1") (pinfunction "1_1") (pintype "passive"))
      (node (ref "R12") (pin "2") (pinfunction "2_2") (pintype "passive"))
    )
    (net (code "49") (name "Net-(I2C-Pad3)") (class "Default")
      (node (ref "I2C") (pin "3") (pinfunction "3_3") (pintype "passive"))
      (node (ref "R11") (pin "2") (pinfunction "2_2") (pintype "passive"))
    )
    (net (code "50") (name "Net-(J1-CC1)") (class "Default")
      (node (ref "J1") (pin "A5") (pinfunction "CC1_A5") (pintype "bidirectional"))
      (node (ref "R2") (pin "2") (pinfunction "2_2") (pintype "passive"))
    )
    (net (code "51") (name "Net-(J1-CC2)") (class "Default")
      (node (ref "J1") (pin "B5") (pinfunction "CC2_B5") (pintype "bidirectional"))
      (node (ref "R1") (pin "2") (pinfunction "2_2") (pintype "passive"))
    )
    (net (code "52") (name "Net-(J1-SHLD-PadSHLD1)") (class "Default")
      (node (ref "J1") (pin "SHLD1") (pinfunction "SHLD_SHLD1") (pintype "bidirectional"))
      (node (ref "J1") (pin "SHLD2") (pinfunction "SHLD_SHLD2") (pintype "bidirectional"))
      (node (ref "J1") (pin "SHLD3") (pinfunction "SHLD_SHLD3") (pintype "bidirectional"))
      (node (ref "J1") (pin "SHLD4") (pinfunction "SHLD_SHLD4") (pintype "bidirectional"))
      (node (ref "SHLD") (pin "2") (pinfunction "2_2") (pintype "passive"))
    )
    (net (code "53") (name "Net-(J4-SIGNAL)") (class "Default")
      (node (ref "J4") (pin "FEED") (pinfunction "SIGNAL_FEED") (pintype "bidirectional"))
      (node (ref "U11") (pin "ANT") (pinfunction "ANT_ANT") (pintype "bidirectional"))
    )
    (net (code "54") (name "Net-(L1-1)") (class "Default")
      (node (ref "L1") (pin "P$1") (pinfunction "1_P$1") (pintype "passive"))
      (node (ref "U2") (pin "3") (pinfunction "LX_3") (pintype "input"))
    )
    (net (code "55") (name "Net-(PWR-Pad2)") (class "Default")
      (node (ref "PWR") (pin "2") (pinfunction "2_2") (pintype "passive"))
      (node (ref "R10") (pin "1") (pinfunction "1_1") (pintype "passive"))
    )
    (net (code "56") (name "Net-(Q1-S)") (class "Default")
      (node (ref "D1") (pin "C") (pinfunction "C_C") (pintype "passive"))
      (node (ref "MEAS") (pin "1") (pinfunction "1_1") (pintype "passive"))
      (node (ref "MEAS") (pin "3") (pinfunction "1_3") (pintype "passive"))
      (node (ref "Q1") (pin "2") (pinfunction "S_2") (pintype "bidirectional"))
    )
    (net (code "57") (name "Net-(Q4-D)") (class "Default")
      (node (ref "Q4") (pin "3") (pinfunction "D_3") (pintype "bidirectional"))
      (node (ref "Q5") (pin "1") (pinfunction "G_1") (pintype "bidirectional"))
      (node (ref "R17") (pin "1") (pinfunction "1_1") (pintype "passive"))
    )
    (net (code "58") (name "Net-(Q6A-B)") (class "Default")
      (node (ref "Q6") (pin "5") (pinfunction "B_5") (pintype "passive"))
      (node (ref "R20") (pin "2") (pinfunction "2_2") (pintype "passive"))
    )
    (net (code "59") (name "Net-(Q6B-B)") (class "Default")
      (node (ref "Q6") (pin "2") (pinfunction "B_2") (pintype "passive"))
      (node (ref "R19") (pin "2") (pinfunction "2_2") (pintype "passive"))
    )
    (net (code "60") (name "Net-(Q10-D)") (class "Default")
      (node (ref "C14") (pin "1") (pinfunction "1_1") (pintype "passive"))
      (node (ref "Q10") (pin "3") (pinfunction "D_3") (pintype "bidirectional"))
      (node (ref "U8") (pin "16") (pinfunction "VCC_16") (pintype "bidirectional"))
    )
    (net (code "61") (name "Net-(Q10-G)") (class "Default")
      (node (ref "Q10") (pin "1") (pinfunction "G_1") (pintype "bidirectional"))
      (node (ref "Q11") (pin "3") (pinfunction "D_3") (pintype "bidirectional"))
      (node (ref "R31") (pin "1") (pinfunction "1_1") (pintype "passive"))
    )
    (net (code "62") (name "Net-(U2-EN)") (class "Default")
      (node (ref "R4") (pin "2") (pinfunction "2_2") (pintype "passive"))
      (node (ref "U2") (pin "1") (pinfunction "EN_1") (pintype "input"))
    )
    (net (code "63") (name "Net-(U2-FB)") (class "Default")
      (node (ref "C2") (pin "1") (pinfunction "1_1") (pintype "passive"))
      (node (ref "R5") (pin "1") (pinfunction "1_1") (pintype "passive"))
      (node (ref "R6") (pin "2") (pinfunction "2_2") (pintype "passive"))
      (node (ref "U2") (pin "5") (pinfunction "FB_5") (pintype "passive"))
    )
    (net (code "64") (name "Net-(U2-VIN)") (class "Default")
      (node (ref "C1") (pin "1") (pinfunction "1_1") (pintype "passive"))
      (node (ref "MEAS") (pin "2") (pinfunction "2_2") (pintype "passive"))
      (node (ref "MEAS") (pin "4") (pinfunction "2_4") (pintype "passive"))
      (node (ref "R4") (pin "1") (pinfunction "1_1") (pintype "passive"))
      (node (ref "U2") (pin "4") (pinfunction "VIN_4") (pintype "input"))
    )
    (net (code "65") (name "Net-(U3-PROG)") (class "Default")
      (node (ref "R8") (pin "2") (pinfunction "2_2") (pintype "passive"))
      (node (ref "U3") (pin "5") (pinfunction "PROG_5") (pintype "input"))
    )
    (net (code "66") (name "Net-(U3-STAT)") (class "Default")
      (node (ref "D3") (pin "C") (pinfunction "C_C") (pintype "passive"))
      (node (ref "U3") (pin "1") (pinfunction "STAT_1") (pintype "output"))
    )
    (net (code "67") (name "Net-(U5-SDO{slash}ADR)") (class "Default")
      (node (ref "BME_ADR") (pin "2") (pinfunction "2_2") (pintype "passive"))
      (node (ref "R13") (pin "1") (pinfunction "1_1") (pintype "passive"))
      (node (ref "U5") (pin "5") (pinfunction "SDO/ADR_5") (pintype "bidirectional"))
    )
    (net (code "68") (name "Net-(U6-AD0{slash}SDO)") (class "Default")
      (node (ref "ICM_ADR") (pin "2") (pinfunction "2_2") (pintype "passive"))
      (node (ref "R14") (pin "1") (pinfunction "1_1") (pintype "passive"))
      (node (ref "U6") (pin "9") (pinfunction "AD0/SDO_9") (pintype "bidirectional"))
    )
    (net (code "69") (name "Net-(U6-REGOUT)") (class "Default")
      (node (ref "C13") (pin "1") (pinfunction "1_1") (pintype "passive"))
      (node (ref "U6") (pin "10") (pinfunction "REGOUT_10") (pintype "bidirectional"))
    )
    (net (code "70") (name "Net-(U8-V3)") (class "Default")
      (node (ref "C6") (pin "1") (pinfunction "1_1") (pintype "passive"))
      (node (ref "U8") (pin "4") (pinfunction "V3_4") (pintype "bidirectional"))
    )
    (net (code "71") (name "Net-(U9-SDO{slash}SA0)") (class "Default")
      (node (ref "ISM_ADR") (pin "2") (pinfunction "2_2") (pintype "passive"))
      (node (ref "R21") (pin "1") (pinfunction "1_1") (pintype "passive"))
      (node (ref "U9") (pin "P1") (pinfunction "SDO/SA0_P1") (pintype "bidirectional"))
    )
    (net (code "72") (name "Net-(U10-CAP)") (class "Default")
      (node (ref "C18") (pin "1") (pinfunction "1_1") (pintype "passive"))
      (node (ref "U10") (pin "10") (pinfunction "CAP_10") (pintype "passive"))
    )
    (net (code "73") (name "Net-(U12-DRDY)") (class "Default")
      (node (ref "D6") (pin "A") (pinfunction "A_A") (pintype "passive"))
      (node (ref "U12") (pin "12") (pinfunction "DRDY_12") (pintype "bidirectional"))
    )
    (net (code "74") (name "Net-(U12-VBG)") (class "Default")
      (node (ref "C19") (pin "1") (pinfunction "1_1") (pintype "passive"))
      (node (ref "U12") (pin "6") (pinfunction "VBG_6") (pintype "bidirectional"))
    )
    (net (code "75") (name "Net-(U12-VIN1N)") (class "Default")
      (node (ref "C20") (pin "1") (pinfunction "1_1") (pintype "passive"))
      (node (ref "R22") (pin "2") (pinfunction "2_2") (pintype "passive"))
      (node (ref "U12") (pin "2") (pinfunction "VIN1N_2") (pintype "bidirectional"))
    )
    (net (code "76") (name "Net-(U12-VIN1P)") (class "Default")
      (node (ref "C20") (pin "2") (pinfunction "2_2") (pintype "passive"))
      (node (ref "R23") (pin "2") (pinfunction "2_2") (pintype "passive"))
      (node (ref "U12") (pin "3") (pinfunction "VIN1P_3") (pintype "bidirectional"))
    )
    (net (code "77") (name "RTS") (class "Default")
      (node (ref "Q6") (pin "4") (pinfunction "E_4") (pintype "passive"))
      (node (ref "R19") (pin "1") (pinfunction "1_1") (pintype "passive"))
      (node (ref "U8") (pin "14") (pinfunction "~{RTS}_14") (pintype "bidirectional"))
    )
    (net (code "78") (name "SCL_1V8") (class "Default")
      (node (ref "Q3") (pin "2") (pinfunction "S_2") (pintype "bidirectional"))
      (node (ref "R16") (pin "1") (pinfunction "1_1") (pintype "passive"))
      (node (ref "U6") (pin "23") (pinfunction "SCL/SCLK_23") (pintype "bidirectional"))
    )
    (net (code "79") (name "SCL_OUT") (class "Default")
      (node (ref "J10") (pin "4") (pinfunction "4_4") (pintype "passive"))
      (node (ref "Q3") (pin "3") (pinfunction "D_3") (pintype "bidirectional"))
      (node (ref "Q9") (pin "2") (pinfunction "S_2") (pintype "bidirectional"))
      (node (ref "R30") (pin "1") (pinfunction "1_1") (pintype "passive"))
      (node (ref "U10") (pin "1") (pinfunction "SCL/SCK_1") (pintype "bidirectional"))
      (node (ref "U12") (pin "13") (pinfunction "SCLK_13") (pintype "bidirectional"))
      (node (ref "U5") (pin "4") (pinfunction "SCK/SCL_4") (pintype "bidirectional"))
      (node (ref "U9") (pin "P13") (pinfunction "SCL_P13") (pintype "bidirectional"))
    )
    (net (code "80") (name "SDA_1V8") (class "Default")
      (node (ref "Q2") (pin "2") (pinfunction "S_2") (pintype "bidirectional"))
      (node (ref "R15") (pin "1") (pinfunction "1_1") (pintype "passive"))
      (node (ref "U6") (pin "24") (pinfunction "SDA/SDI_24") (pintype "bidirectional"))
    )
    (net (code "81") (name "SDA_OUT") (class "Default")
      (node (ref "J10") (pin "3") (pinfunction "3_3") (pintype "passive"))
      (node (ref "Q2") (pin "3") (pinfunction "D_3") (pintype "bidirectional"))
      (node (ref "Q8") (pin "2") (pinfunction "S_2") (pintype "bidirectional"))
      (node (ref "R29") (pin "1") (pinfunction "1_1") (pintype "passive"))
      (node (ref "U10") (pin "16") (pinfunction "SDA/SDI_16") (pintype "bidirectional"))
      (node (ref "U12") (pin "14") (pinfunction "SDIO_14") (pintype "bidirectional"))
      (node (ref "U5") (pin "3") (pinfunction "SDI/SDA_3") (pintype "bidirectional"))
      (node (ref "U9") (pin "P14") (pinfunction "SDA/SDI/SDO_P14") (pintype "bidirectional"))
    )
    (net (code "82") (name "USB_DN") (class "Default")
      (node (ref "J1") (pin "A7") (pinfunction "D-_A7") (pintype "bidirectional"))
      (node (ref "J1") (pin "B7") (pinfunction "D-_B7") (pintype "bidirectional"))
      (node (ref "U8") (pin "6") (pinfunction "UD-_6") (pintype "bidirectional"))
    )
    (net (code "83") (name "USB_DP") (class "Default")
      (node (ref "J1") (pin "A6") (pinfunction "D+_A6") (pintype "bidirectional"))
      (node (ref "J1") (pin "B6") (pinfunction "D+_B6") (pintype "bidirectional"))
      (node (ref "U8") (pin "5") (pinfunction "UD+_5") (pintype "bidirectional"))
    )
    (net (code "84") (name "VDDA") (class "Default")
      (node (ref "C22") (pin "1") (pinfunction "1_1") (pintype "passive"))
      (node (ref "C23") (pin "1") (pinfunction "1_1") (pintype "passive"))
      (node (ref "J5") (pin "6") (pinfunction "6_6") (pintype "bidirectional"))
      (node (ref "J5") (pin "7") (pinfunction "7_7") (pintype "bidirectional"))
      (node (ref "U12") (pin "1") (pinfunction "REFP_1") (pintype "bidirectional"))
      (node (ref "U12") (pin "16") (pinfunction "AVDD_16") (pintype "bidirectional"))
    )
    (net (code "85") (name "VOUT") (class "Default")
      (node (ref "C15") (pin "1") (pinfunction "1_1") (pintype "passive"))
      (node (ref "C16") (pin "1") (pinfunction "1_1") (pintype "passive"))
      (node (ref "C17") (pin "1") (pinfunction "1_1") (pintype "passive"))
      (node (ref "C7") (pin "1") (pinfunction "1_1") (pintype "passive"))
      (node (ref "C8") (pin "1") (pinfunction "1_1") (pintype "passive"))
      (node (ref "C9") (pin "1") (pinfunction "1_1") (pintype "passive"))
      (node (ref "J10") (pin "2") (pinfunction "2_2") (pintype "power_in"))
      (node (ref "J12") (pin "3") (pinfunction "1_3") (pintype "passive"))
      (node (ref "J7") (pin "5") (pinfunction "5_5") (pintype "bidirectional"))
      (node (ref "J9") (pin "5") (pinfunction "5_5") (pintype "bidirectional"))
      (node (ref "Q5") (pin "2") (pinfunction "S_2") (pintype "bidirectional"))
      (node (ref "Q7") (pin "3") (pinfunction "D_3") (pintype "bidirectional"))
      (node (ref "Q8") (pin "1") (pinfunction "G_1") (pintype "bidirectional"))
      (node (ref "Q9") (pin "1") (pinfunction "G_1") (pintype "bidirectional"))
      (node (ref "R13") (pin "2") (pinfunction "2_2") (pintype "passive"))
      (node (ref "R17") (pin "2") (pinfunction "2_2") (pintype "passive"))
      (node (ref "R21") (pin "2") (pinfunction "2_2") (pintype "passive"))
      (node (ref "R29") (pin "2") (pinfunction "2_2") (pintype "passive"))
      (node (ref "R30") (pin "2") (pinfunction "2_2") (pintype "passive"))
      (node (ref "U10") (pin "13") (pinfunction "VDDIO_13") (pintype "power_in"))
      (node (ref "U10") (pin "2") (pinfunction "VDD_2") (pintype "power_in"))
      (node (ref "U10") (pin "4") (pinfunction "~{SPI_CS}_4") (pintype "input"))
      (node (ref "U11") (pin "3.3V") (pinfunction "3.3V_3.3V") (pintype "bidirectional"))
      (node (ref "U12") (pin "15") (pinfunction "DVDD_15") (pintype "bidirectional"))
      (node (ref "U5") (pin "2") (pinfunction "~{CS}_2") (pintype "bidirectional"))
      (node (ref "U5") (pin "6") (pinfunction "VDDIO_6") (pintype "bidirectional"))
      (node (ref "U5") (pin "8") (pinfunction "VDD_8") (pintype "bidirectional"))
      (node (ref "U7") (pin "1") (pinfunction "IN_1") (pintype "input"))
      (node (ref "U7") (pin "3") (pinfunction "EN_3") (pintype "input"))
      (node (ref "U9") (pin "P12") (pinfunction "~{CS}_P12") (pintype "bidirectional"))
      (node (ref "U9") (pin "P5") (pinfunction "VDD_IO_P5") (pintype "power_in"))
      (node (ref "U9") (pin "P8") (pinfunction "VDD_P8") (pintype "power_in"))
    )
    (net (code "86") (name "V_BATT") (class "Default")
      (node (ref "C5") (pin "1") (pinfunction "1_1") (pintype "passive"))
      (node (ref "J2") (pin "2") (pinfunction "+_2") (pintype "bidirectional"))
      (node (ref "J6") (pin "1") (pinfunction "1_1") (pintype "passive"))
      (node (ref "Q1") (pin "3") (pinfunction "D_3") (pintype "bidirectional"))
      (node (ref "R25") (pin "2") (pinfunction "2_2") (pintype "passive"))
      (node (ref "U3") (pin "3") (pinfunction "VBAT_3") (pintype "power_in"))
    )
    (net (code "87") (name "V_USB") (class "Default")
      (node (ref "D5") (pin "A") (pinfunction "A_A") (pintype "passive"))
      (node (ref "J1") (pin "VBUS1") (pinfunction "VBUS_VBUS1") (pintype "bidirectional"))
      (node (ref "J1") (pin "VBUS2") (pinfunction "VBUS_VBUS2") (pintype "bidirectional"))
      (node (ref "Q11") (pin "1") (pinfunction "G_1") (pintype "bidirectional"))
    )
    (net (code "88") (name "unconnected-(J2-PAD1-PadNC1)") (class "Default")
      (node (ref "J2") (pin "NC1") (pinfunction "PAD1_NC1") (pintype "bidirectional"))
    )
    (net (code "89") (name "unconnected-(J2-PAD2-PadNC2)") (class "Default")
      (node (ref "J2") (pin "NC2") (pinfunction "PAD2_NC2") (pintype "bidirectional"))
    )
    (net (code "90") (name "unconnected-(J9-Pad6)") (class "Default")
      (node (ref "J9") (pin "6") (pinfunction "6_6") (pintype "bidirectional"))
    )
    (net (code "91") (name "unconnected-(U6-AUX_CL-Pad7)") (class "Default")
      (node (ref "U6") (pin "7") (pinfunction "AUX_CL_7") (pintype "bidirectional"))
    )
    (net (code "92") (name "unconnected-(U6-AUX_DA-Pad21)") (class "Default")
      (node (ref "U6") (pin "21") (pinfunction "AUX_DA_21") (pintype "bidirectional"))
    )
    (net (code "93") (name "unconnected-(U6-FSYNC-Pad11)") (class "Default")
      (node (ref "U6") (pin "11") (pinfunction "FSYNC_11") (pintype "bidirectional"))
    )
    (net (code "94") (name "unconnected-(U8-R232-Pad15)") (class "Default")
      (node (ref "U8") (pin "15") (pinfunction "R232_15") (pintype "bidirectional"))
    )
    (net (code "95") (name "unconnected-(U8-~{CTS}-Pad9)") (class "Default")
      (node (ref "U8") (pin "9") (pinfunction "~{CTS}_9") (pintype "bidirectional"))
    )
    (net (code "96") (name "unconnected-(U8-~{DCD}-Pad12)") (class "Default")
      (node (ref "U8") (pin "12") (pinfunction "~{DCD}_12") (pintype "bidirectional"))
    )
    (net (code "97") (name "unconnected-(U8-~{DSR}-Pad10)") (class "Default")
      (node (ref "U8") (pin "10") (pinfunction "~{DSR}_10") (pintype "bidirectional"))
    )
    (net (code "98") (name "unconnected-(U8-~{RI}-Pad11)") (class "Default")
      (node (ref "U8") (pin "11") (pinfunction "~{RI}_11") (pintype "bidirectional"))
    )
    (net (code "99") (name "unconnected-(U9-OCS_AUX-PadP10)") (class "Default")
      (node (ref "U9") (pin "P10") (pinfunction "OCS_AUX_P10") (pintype "bidirectional"))
    )
    (net (code "100") (name "unconnected-(U9-SCX-PadP3)") (class "Default")
      (node (ref "U9") (pin "P3") (pinfunction "SCX_P3") (pintype "bidirectional"))
    )
    (net (code "101") (name "unconnected-(U9-SDO_AUX-PadP11)") (class "Default")
      (node (ref "U9") (pin "P11") (pinfunction "SDO_AUX_P11") (pintype "bidirectional"))
    )
    (net (code "102") (name "unconnected-(U9-SDX-PadP2)") (class "Default")
      (node (ref "U9") (pin "P2") (pinfunction "SDX_P2") (pintype "bidirectional"))
    )
    (net (code "103") (name "unconnected-(U10-SDO-Pad5)") (class "Default")
      (node (ref "U10") (pin "5") (pinfunction "SDO_5") (pintype "output"))
    )
    (net (code "104") (name "unconnected-(U11-PadDIO2)") (class "Default")
      (node (ref "U11") (pin "DIO2") (pinfunction "DIO2_DIO2") (pintype "bidirectional"))
    )
    (net (code "105") (name "unconnected-(U11-PadDIO3)") (class "Default")
      (node (ref "U11") (pin "DIO3") (pinfunction "DIO3_DIO3") (pintype "bidirectional"))
    )
    (net (code "106") (name "unconnected-(U11-PadDIO4)") (class "Default")
      (node (ref "U11") (pin "DIO4") (pinfunction "DIO4_DIO4") (pintype "bidirectional"))
    )
    (net (code "107") (name "unconnected-(U11-PadDIO5)") (class "Default")
      (node (ref "U11") (pin "DIO5") (pinfunction "DIO5_DIO5") (pintype "bidirectional"))
    )
    (net (code "108") (name "unconnected-(U12-XIN-Pad10)") (class "Default")
      (node (ref "U12") (pin "10") (pinfunction "XIN_10") (pintype "bidirectional"))
    )
    (net (code "109") (name "unconnected-(U12-XOUT-Pad11)") (class "Default")
      (node (ref "U12") (pin "11") (pinfunction "XOUT_11") (pintype "bidirectional"))
    )
  )
)
